# KNX-MultiExt.net
KiCad netlist of a schematic drawn in Altium Designer
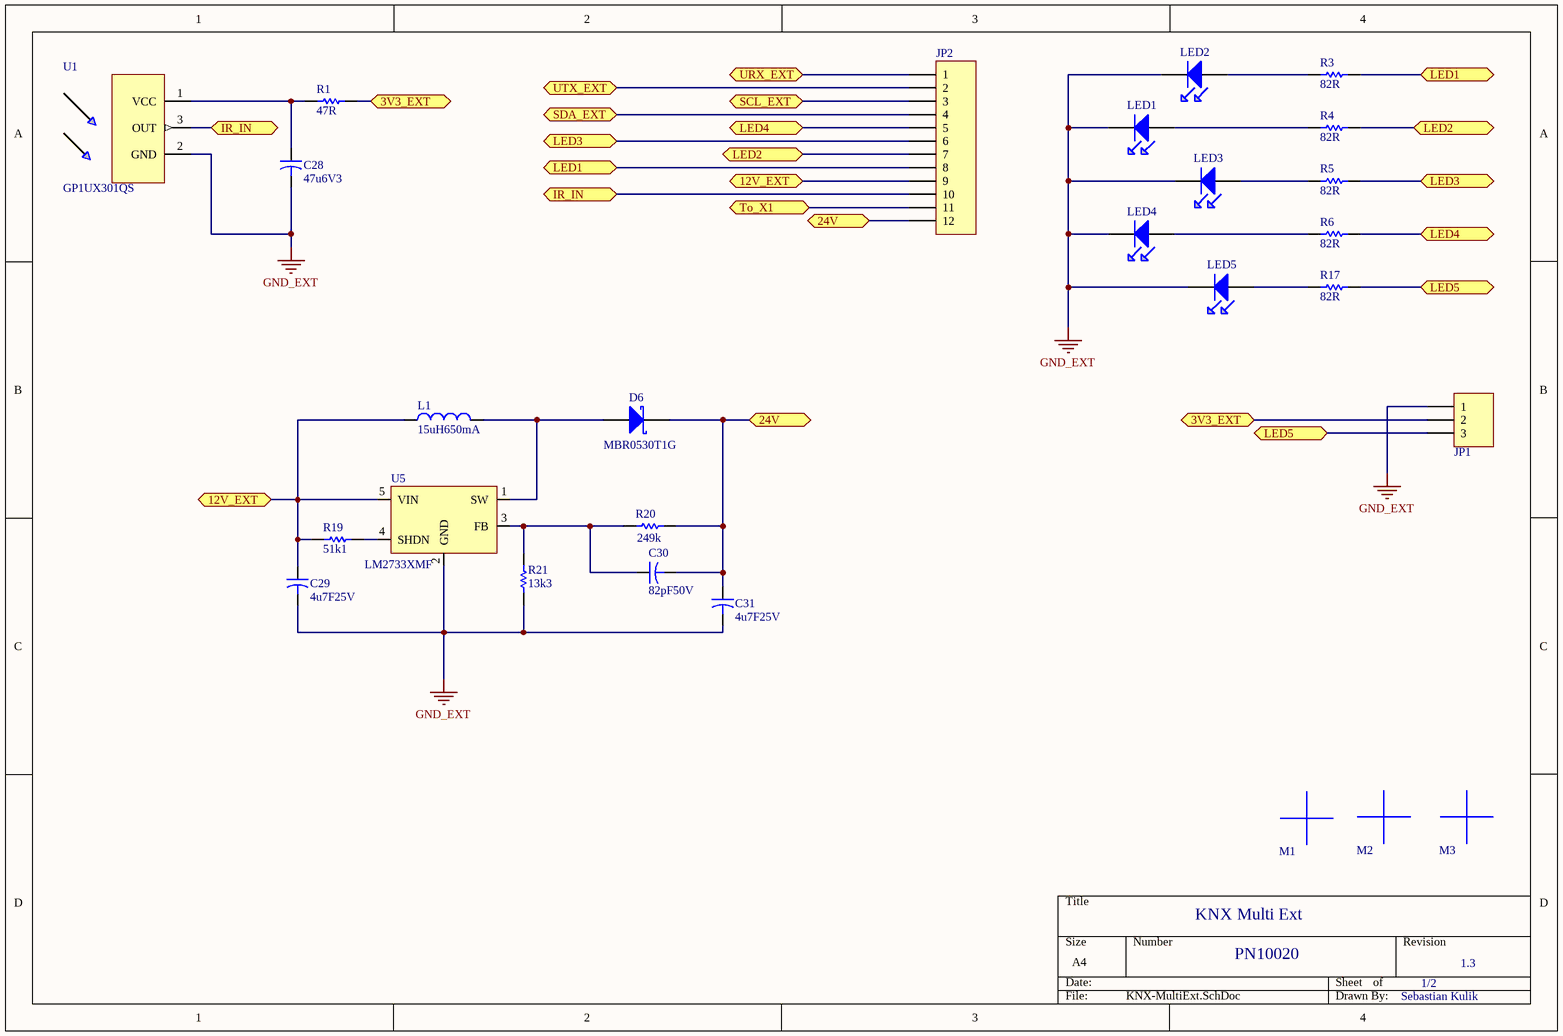
[diagram p0: KNX-MultiExt.SchDoc]

(export (version "E")
  (design (tool "Eeschema 10.0.6"))
  (components
    (comp (ref "C28")
      (value "47u6V3")
      (footprint "C0805")
      (description "Kemet  C series, X5R, 20%, 6.3V")
      (fields
        (field (name "MANUFACTURER") "Kemet")
        (field (name "Comment") "47u6V3_0805")
        (field (name "PUBLISHER") "Sebastian Kulik")
      )
      (libsource (lib "Capacitors") (part "47u6V3_0805"))
    )
    (comp (ref "C29")
      (value "4u7F25V")
      (footprint "C0805")
      (description "GRM series, X5R, 10%, 25V")
      (fields
        (field (name "MANUFACTURER") "Murata")
        (field (name "Comment") "4u7F25V_0805_Murata")
        (field (name "PUBLISHER") "Sebastian Kulik")
      )
      (libsource (lib "Capacitors") (part "4u7F25V_0805_Murata"))
    )
    (comp (ref "C30")
      (value "82pF50V")
      (footprint "C0805")
      (description "C0G series, 5%, 50V")
      (fields
        (field (name "MANUFACTURER") "AVX")
        (field (name "Comment") "82pF50V_0805")
        (field (name "PUBLISHER") "Sebastian Kulik")
      )
      (libsource (lib "Capacitors") (part "82pF50V_0805"))
    )
    (comp (ref "C31")
      (value "4u7F25V")
      (footprint "C0805")
      (description "TDK  C series, X7R, 10%, 25V")
      (fields
        (field (name "MANUFACTURER") "TDK")
        (field (name "Comment") "4u7F25V_0805")
        (field (name "PUBLISHER") "Sebastian Kulik")
      )
      (libsource (lib "Capacitors") (part "4u7F25V_0805"))
    )
    (comp (ref "D6")
      (value "MBR0530T1G")
      (footprint "SOD123")
      (description "Diode Schottky,2A,40V")
      (fields (field (name "MANUFACTURER") "Rohm") (field (name "PUBLISHER") "Sebastian Kulik"))
      (libsource (lib "Discrete") (part "MBR0530T1G"))
    )
    (comp (ref "JP1")
      (value "Plug_3_90_2.54")
      (footprint "HDR1X3-DOWN")
      (description "Plug,-3-Pin")
      (fields (field (name "MANUFACTURER") "WE") (field (name "PUBLISHER") "Sebastian Kulik"))
      (libsource (lib "Connectors") (part "Plug_3_90_2.54"))
    )
    (comp (ref "JP2")
      (value "Plug_12_90_2.54")
      (footprint "HDR1X12_2.54-Down")
      (description "Plug, 11-Pin")
      (fields (field (name "MANUFACTURER") "WE") (field (name "PUBLISHER") "Sebastian Kulik"))
      (libsource (lib "Connectors") (part "Plug_12_90_2.54"))
    )
    (comp (ref "L1")
      (value "15uH650mA")
      (footprint "WE-TPC-3816")
      (description "Coil, 15uH, 0.65A")
      (fields
        (field (name "MANUFACTURER") "WE")
        (field (name "Comment") "15uH-WE-TPC")
        (field (name "PUBLISHER") "Sebastian Kulik")
      )
      (libsource (lib "Passives") (part "15uH-WE-TPC"))
    )
    (comp (ref "LED1")
      (value "HSMG-120-Y")
      (footprint "HSMA-120-OR")
      (description "LED, 90°, yellow")
      (fields (field (name "MANUFACTURER") "Avago") (field (name "PUBLISHER") "Sebastian Kulik"))
      (libsource (lib "Discrete") (part "HSMG-120-Y"))
    )
    (comp (ref "LED2")
      (value "HSMG-120-GR")
      (footprint "HSMA-120-G")
      (description "LED, 90°, green")
      (fields (field (name "MANUFACTURER") "Avago") (field (name "PUBLISHER") "Sebastian Kulik"))
      (libsource (lib "Discrete") (part "HSMG-120-GR"))
    )
    (comp (ref "LED3")
      (value "HSMG-120-Y")
      (footprint "HSMA-120-OR")
      (description "LED, 90°, yellow")
      (fields (field (name "MANUFACTURER") "Avago") (field (name "PUBLISHER") "Sebastian Kulik"))
      (libsource (lib "Discrete") (part "HSMG-120-Y"))
    )
    (comp (ref "LED4")
      (value "HSMG-120-Y")
      (footprint "HSMA-120-OR")
      (description "LED, 90°, yellow")
      (fields (field (name "MANUFACTURER") "Avago") (field (name "PUBLISHER") "Sebastian Kulik"))
      (libsource (lib "Discrete") (part "HSMG-120-Y"))
    )
    (comp (ref "LED5")
      (value "HSMG-120-Y")
      (footprint "HSMA-120-OR")
      (description "LED, 90°, yellow")
      (fields (field (name "MANUFACTURER") "Avago") (field (name "PUBLISHER") "Sebastian Kulik"))
      (libsource (lib "Discrete") (part "HSMG-120-Y"))
    )
    (comp (ref "M1") (value "PasteMark") (footprint "Mark-3mm") (libsource (lib "Symbols") (part "Mark")))
    (comp (ref "M2") (value "PasteMark") (footprint "Mark-3mm") (libsource (lib "Symbols") (part "Mark")))
    (comp (ref "M3") (value "PasteMark") (footprint "Mark-3mm") (libsource (lib "Symbols") (part "Mark")))
    (comp (ref "R1")
      (value "47R")
      (footprint "R0603(1608)")
      (description "Vishay, CRCW series, 100mW, 1%")
      (fields
        (field (name "MANUFACTURER") "Vishay")
        (field (name "Comment") "47R_0603")
        (field (name "PUBLISHER") "Sebastian Kulik")
      )
      (libsource (lib "Resistors") (part "47R_0603"))
    )
    (comp (ref "R3")
      (value "82R")
      (footprint "R0603(1608)")
      (description "Vishay, CRCW series, 100mW, 1%")
      (fields
        (field (name "MANUFACTURER") "Vishay")
        (field (name "Comment") "82R_0603")
        (field (name "PUBLISHER") "Sebastian Kulik")
      )
      (libsource (lib "Resistors") (part "82R_0603"))
    )
    (comp (ref "R4")
      (value "82R")
      (footprint "R0603(1608)")
      (description "Vishay, CRCW series, 100mW, 1%")
      (fields
        (field (name "MANUFACTURER") "Vishay")
        (field (name "Comment") "82R_0603")
        (field (name "PUBLISHER") "Sebastian Kulik")
      )
      (libsource (lib "Resistors") (part "82R_0603"))
    )
    (comp (ref "R5")
      (value "82R")
      (footprint "R0603(1608)")
      (description "Vishay, CRCW series, 100mW, 1%")
      (fields
        (field (name "MANUFACTURER") "Vishay")
        (field (name "Comment") "82R_0603")
        (field (name "PUBLISHER") "Sebastian Kulik")
      )
      (libsource (lib "Resistors") (part "82R_0603"))
    )
    (comp (ref "R6")
      (value "82R")
      (footprint "R0603(1608)")
      (description "Vishay, CRCW series, 100mW, 1%")
      (fields
        (field (name "MANUFACTURER") "Vishay")
        (field (name "Comment") "82R_0603")
        (field (name "PUBLISHER") "Sebastian Kulik")
      )
      (libsource (lib "Resistors") (part "82R_0603"))
    )
    (comp (ref "R17")
      (value "82R")
      (footprint "R0603(1608)")
      (description "Vishay, CRCW series, 100mW, 1%")
      (fields
        (field (name "MANUFACTURER") "Vishay")
        (field (name "Comment") "82R_0603")
        (field (name "PUBLISHER") "Sebastian Kulik")
      )
      (libsource (lib "Resistors") (part "82R_0603"))
    )
    (comp (ref "R19")
      (value "51k1")
      (footprint "R0402")
      (description "Vishay CRCW series, 63mW, 1%")
      (fields
        (field (name "MANUFACTURER") "Vishay")
        (field (name "Comment") "51k1_0402")
        (field (name "PUBLISHER") "Sebastian Kulik")
      )
      (libsource (lib "Resistors") (part "51k1_0402"))
    )
    (comp (ref "R20")
      (value "249k")
      (footprint "R0402")
      (description "Vishay CRCW series, 63mW, 1%")
      (fields
        (field (name "MANUFACTURER") "Vishay")
        (field (name "Comment") "249k_0402")
        (field (name "PUBLISHER") "Sebastian Kulik")
      )
      (libsource (lib "Resistors") (part "249k_0402"))
    )
    (comp (ref "R21")
      (value "13k3")
      (footprint "R0402")
      (description "Vishay CRCW series, 63mW, 1%")
      (fields
        (field (name "MANUFACTURER") "Vishay")
        (field (name "Comment") "13k3_0402")
        (field (name "PUBLISHER") "Sebastian Kulik")
      )
      (libsource (lib "Resistors") (part "13k3_0402"))
    )
    (comp (ref "U1")
      (value "GP1UX301QS")
      (footprint "IR-GP")
      (description "IR reseiver")
      (fields (field (name "MANUFACTURER") "Sharp") (field (name "PUBLISHER") "Sebastian Kulik"))
      (libsource (lib "ICs") (part "GP1UX301QS"))
    )
    (comp (ref "U5")
      (value "LM2733XMF")
      (footprint "PDSO-G5")
      (description "TI, buck boost converter, 1A max")
      (fields (field (name "MANUFACTURER") "TI") (field (name "PUBLISHER") "Sebastian Kulik"))
      (libsource (lib "ICs") (part "LM2733XMF"))
    )
  )
  (nets
    (net (code "1") (name "/3V3_EXT") (class "Default")
      (node (ref "JP1") (pin "2") (pinfunction "2_2") (pintype "passive"))
      (node (ref "R1") (pin "2") (pinfunction "2_2") (pintype "passive"))
    )
    (net (code "2") (name "/12V_EXT") (class "Default")
      (node (ref "C29") (pin "1") (pinfunction "1_1") (pintype "passive"))
      (node (ref "JP2") (pin "9") (pinfunction "9_9") (pintype "passive"))
      (node (ref "L1") (pin "1") (pinfunction "1_1") (pintype "passive"))
      (node (ref "R19") (pin "1") (pinfunction "1_1") (pintype "passive"))
      (node (ref "U5") (pin "5") (pinfunction "VIN_5") (pintype "passive"))
    )
    (net (code "3") (name "/24V") (class "Default")
      (node (ref "C30") (pin "2") (pinfunction "2_2") (pintype "passive"))
      (node (ref "C31") (pin "1") (pinfunction "1_1") (pintype "passive"))
      (node (ref "D6") (pin "1") (pinfunction "K_1") (pintype "passive"))
      (node (ref "JP2") (pin "12") (pinfunction "12_12") (pintype "passive"))
      (node (ref "R20") (pin "2") (pinfunction "2_2") (pintype "passive"))
    )
    (net (code "4") (name "/IR_IN") (class "Default")
      (node (ref "JP2") (pin "10") (pinfunction "10_10") (pintype "passive"))
      (node (ref "U1") (pin "3") (pinfunction "OUT_3") (pintype "output"))
    )
    (net (code "5") (name "/LED1") (class "Default")
      (node (ref "JP2") (pin "8") (pinfunction "8_8") (pintype "passive"))
      (node (ref "R3") (pin "2") (pinfunction "2_2") (pintype "passive"))
    )
    (net (code "6") (name "/LED2") (class "Default")
      (node (ref "JP2") (pin "7") (pinfunction "7_7") (pintype "passive"))
      (node (ref "R4") (pin "2") (pinfunction "2_2") (pintype "passive"))
    )
    (net (code "7") (name "/LED3") (class "Default")
      (node (ref "JP2") (pin "6") (pinfunction "6_6") (pintype "passive"))
      (node (ref "R5") (pin "2") (pinfunction "2_2") (pintype "passive"))
    )
    (net (code "8") (name "/LED4") (class "Default")
      (node (ref "JP2") (pin "5") (pinfunction "5_5") (pintype "passive"))
      (node (ref "R6") (pin "2") (pinfunction "2_2") (pintype "passive"))
    )
    (net (code "9") (name "/LED5") (class "Default")
      (node (ref "JP1") (pin "3") (pinfunction "3_3") (pintype "passive"))
      (node (ref "R17") (pin "2") (pinfunction "2_2") (pintype "passive"))
    )
    (net (code "10") (name "/SCL_EXT") (class "Default")
      (node (ref "JP2") (pin "3") (pinfunction "3_3") (pintype "passive"))
    )
    (net (code "11") (name "/SDA_EXT") (class "Default")
      (node (ref "JP2") (pin "4") (pinfunction "4_4") (pintype "passive"))
    )
    (net (code "12") (name "/To_X1") (class "Default")
      (node (ref "JP2") (pin "11") (pinfunction "11_11") (pintype "passive"))
    )
    (net (code "13") (name "/URX_EXT") (class "Default")
      (node (ref "JP2") (pin "1") (pinfunction "1_1") (pintype "passive"))
    )
    (net (code "14") (name "/UTX_EXT") (class "Default")
      (node (ref "JP2") (pin "2") (pinfunction "2_2") (pintype "passive"))
    )
    (net (code "15") (name "GND_EXT") (class "Default")
      (node (ref "C28") (pin "2") (pinfunction "2_2") (pintype "passive"))
      (node (ref "C29") (pin "2") (pinfunction "2_2") (pintype "passive"))
      (node (ref "C31") (pin "2") (pinfunction "2_2") (pintype "passive"))
      (node (ref "JP1") (pin "1") (pinfunction "1_1") (pintype "passive"))
      (node (ref "LED1") (pin "1") (pinfunction "K_1") (pintype "passive"))
      (node (ref "LED2") (pin "1") (pinfunction "K_1") (pintype "passive"))
      (node (ref "LED3") (pin "1") (pinfunction "K_1") (pintype "passive"))
      (node (ref "LED4") (pin "1") (pinfunction "K_1") (pintype "passive"))
      (node (ref "LED5") (pin "1") (pinfunction "K_1") (pintype "passive"))
      (node (ref "R21") (pin "1") (pinfunction "1_1") (pintype "passive"))
      (node (ref "U1") (pin "2") (pinfunction "GND_2") (pintype "power_in"))
      (node (ref "U5") (pin "2") (pinfunction "GND_2") (pintype "passive"))
    )
    (net (code "16") (name "Net-(D6-A)") (class "Default")
      (node (ref "D6") (pin "2") (pinfunction "A_2") (pintype "passive"))
      (node (ref "L1") (pin "2") (pinfunction "2_2") (pintype "passive"))
      (node (ref "U5") (pin "1") (pinfunction "SW_1") (pintype "power_in"))
    )
    (net (code "17") (name "Net-(LED1-A)") (class "Default")
      (node (ref "LED1") (pin "2") (pinfunction "A_2") (pintype "passive"))
      (node (ref "R4") (pin "1") (pinfunction "1_1") (pintype "passive"))
    )
    (net (code "18") (name "Net-(LED2-A)") (class "Default")
      (node (ref "LED2") (pin "2") (pinfunction "A_2") (pintype "passive"))
      (node (ref "R3") (pin "1") (pinfunction "1_1") (pintype "passive"))
    )
    (net (code "19") (name "Net-(LED3-A)") (class "Default")
      (node (ref "LED3") (pin "2") (pinfunction "A_2") (pintype "passive"))
      (node (ref "R5") (pin "1") (pinfunction "1_1") (pintype "passive"))
    )
    (net (code "20") (name "Net-(LED4-A)") (class "Default")
      (node (ref "LED4") (pin "2") (pinfunction "A_2") (pintype "passive"))
      (node (ref "R6") (pin "1") (pinfunction "1_1") (pintype "passive"))
    )
    (net (code "21") (name "Net-(LED5-A)") (class "Default")
      (node (ref "LED5") (pin "2") (pinfunction "A_2") (pintype "passive"))
      (node (ref "R17") (pin "1") (pinfunction "1_1") (pintype "passive"))
    )
    (net (code "22") (name "Net-(U1-VCC)") (class "Default")
      (node (ref "C28") (pin "1") (pinfunction "1_1") (pintype "passive"))
      (node (ref "R1") (pin "1") (pinfunction "1_1") (pintype "passive"))
      (node (ref "U1") (pin "1") (pinfunction "VCC_1") (pintype "power_in"))
    )
    (net (code "23") (name "Net-(U5-FB)") (class "Default")
      (node (ref "C30") (pin "1") (pinfunction "1_1") (pintype "passive"))
      (node (ref "R20") (pin "1") (pinfunction "1_1") (pintype "passive"))
      (node (ref "R21") (pin "2") (pinfunction "2_2") (pintype "passive"))
      (node (ref "U5") (pin "3") (pinfunction "FB_3") (pintype "passive"))
    )
    (net (code "24") (name "Net-(U5-SHDN)") (class "Default")
      (node (ref "R19") (pin "2") (pinfunction "2_2") (pintype "passive"))
      (node (ref "U5") (pin "4") (pinfunction "SHDN_4") (pintype "passive"))
    )
  )
)
